# EVT_Rev_A_Shock_Measurement.net
KiCad netlist of a schematic drawn in EasyEDA Pro
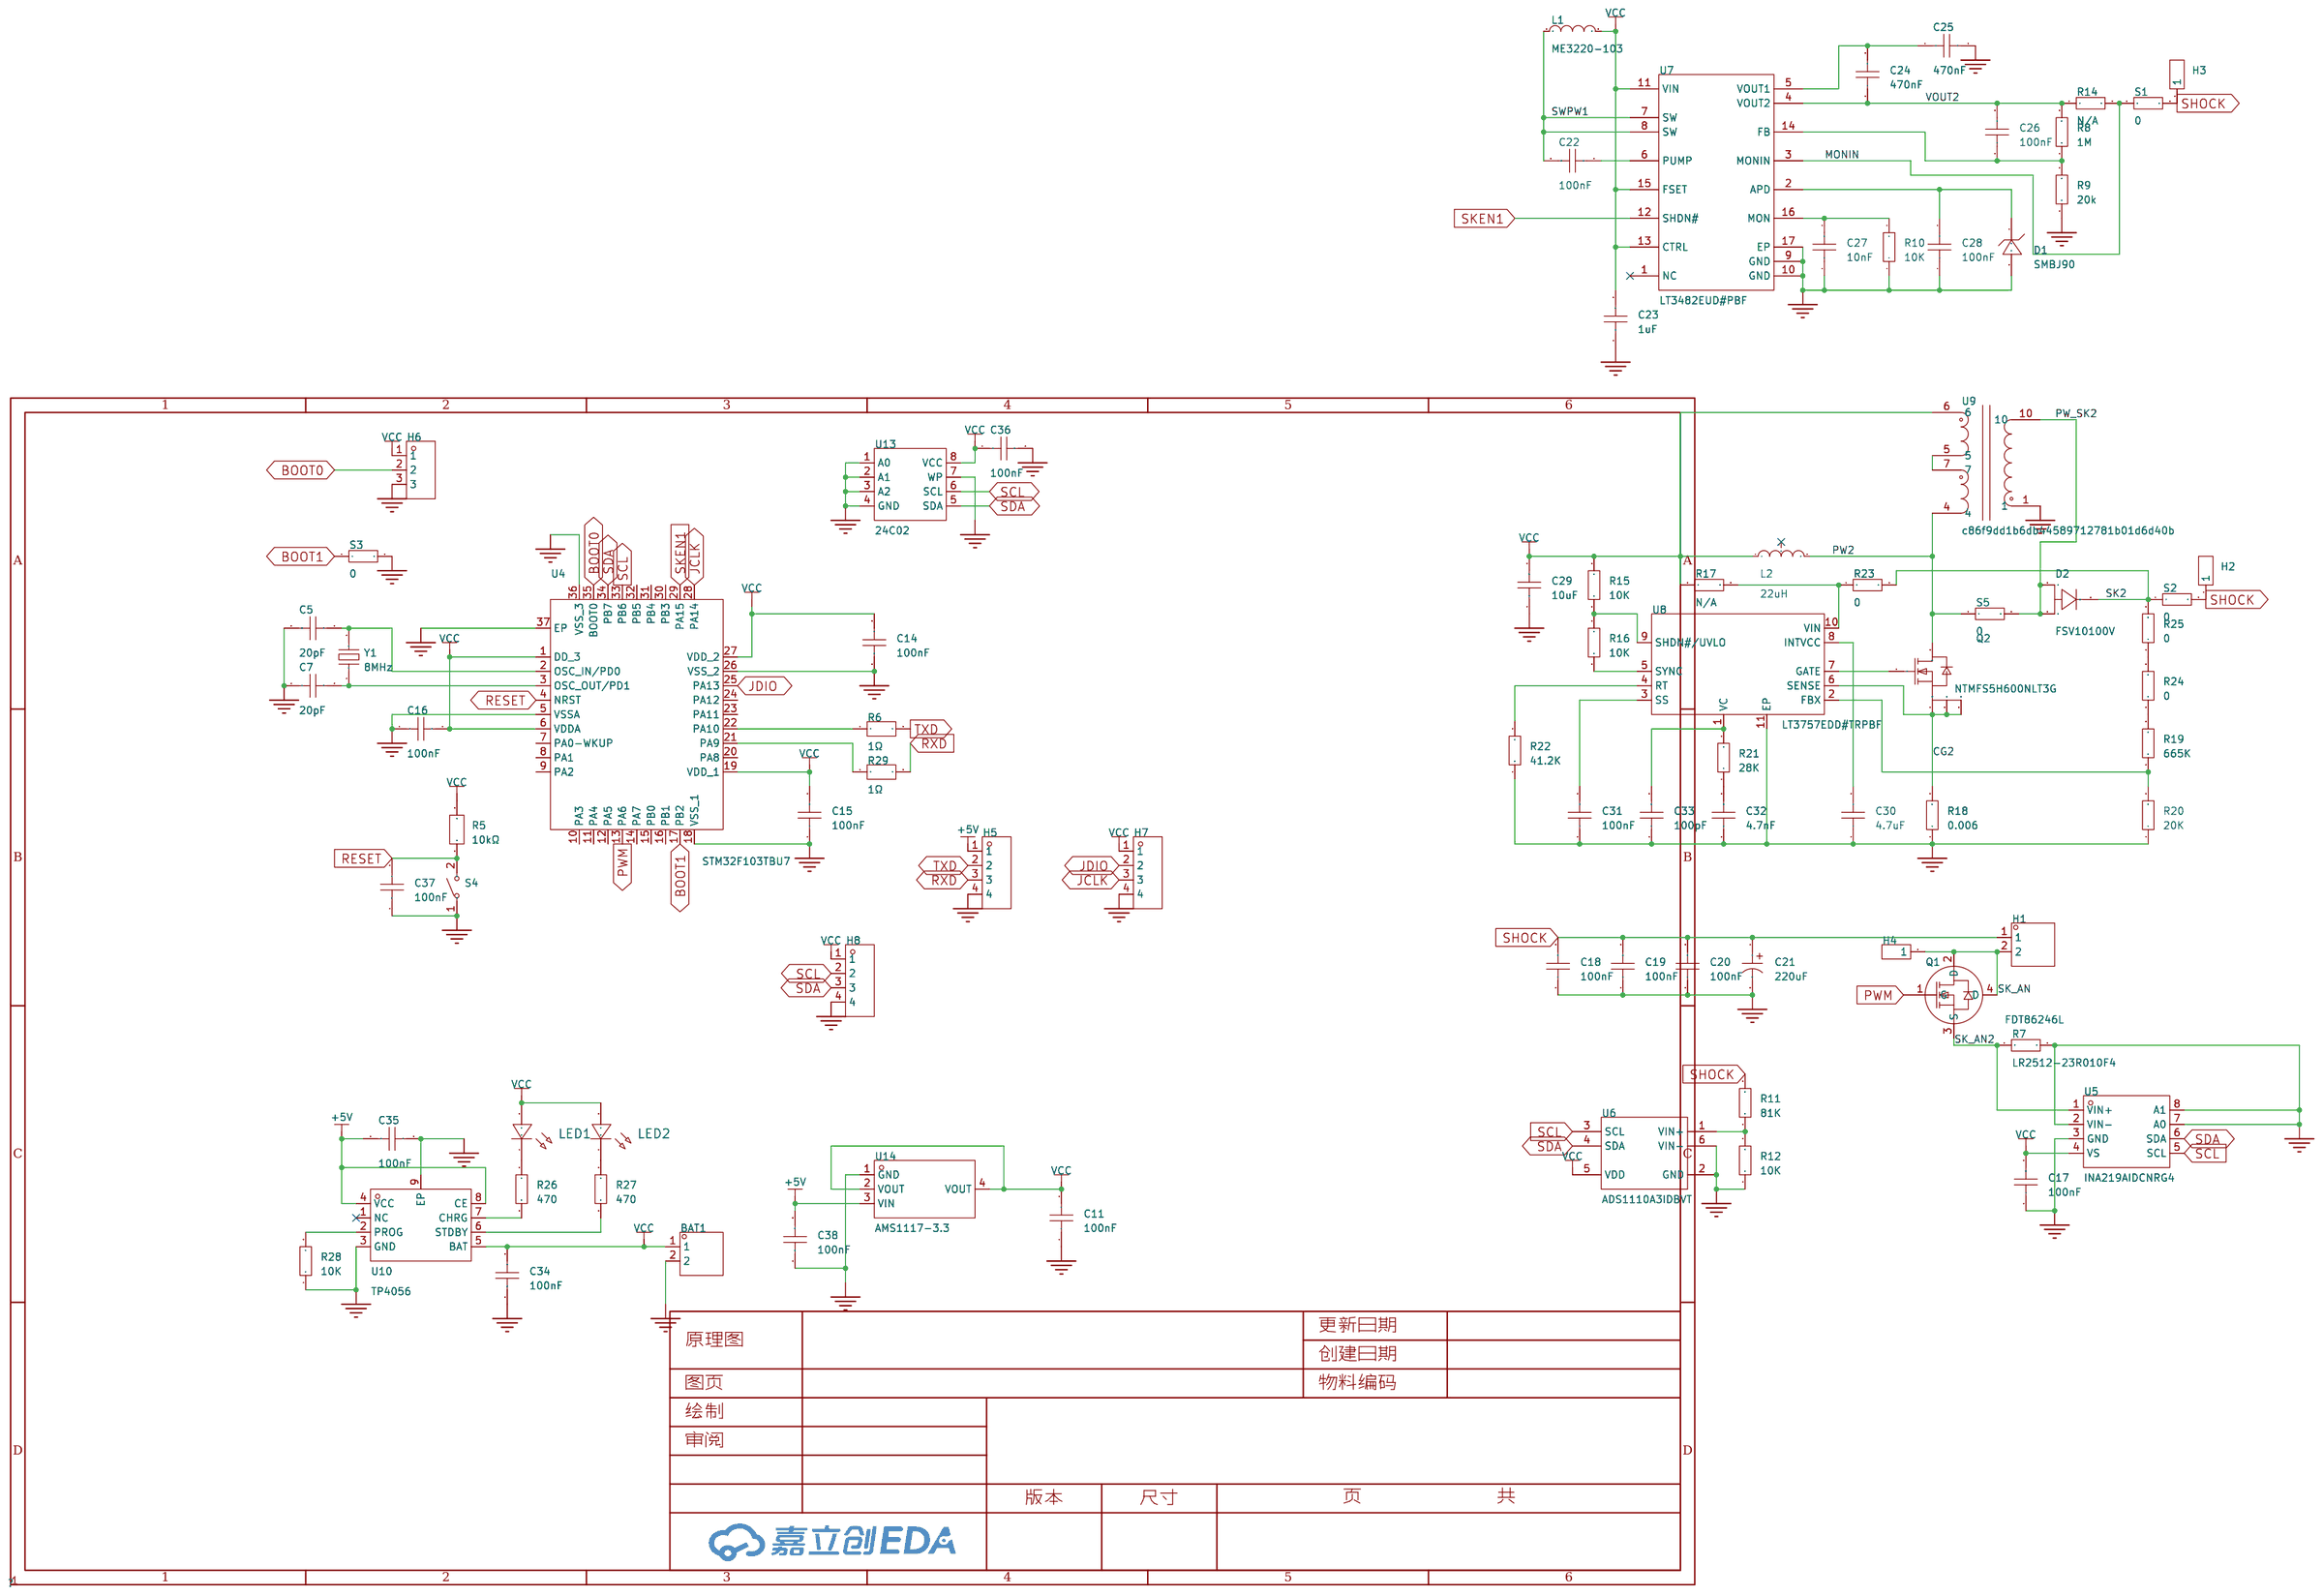
[diagram p0: schematic sheet]

(export (version "E")
  (design (tool "Eeschema 10.0.6"))
  (components
    (comp (ref "BAT1")
      (value "~")
      (footprint "easyedapro:HDR-TH_2P-P2.54-V-M-1")
      (libsource (lib "easyedapro") (part "210S-1*2P L=11.6MMGold-plated black"))
    )
    (comp (ref "C5")
      (value "20pF")
      (footprint "easyedapro:C0603")
      (description "容值:20pF;精度:±5%;额定电压:50V;材质(温度系数):C0G;")
      (fields
        (field (name "Manufacturer Part") "CSA0603C0G200J500JT")
        (field (name "Manufacturer") "HRE(芯声)")
      )
      (libsource (lib "easyedapro") (part "CSA0603C0G200J500JT"))
    )
    (comp (ref "C7")
      (value "20pF")
      (footprint "easyedapro:C0603")
      (description "容值:20pF;精度:±5%;额定电压:50V;材质(温度系数):C0G;")
      (fields
        (field (name "Manufacturer Part") "CSA0603C0G200J500JT")
        (field (name "Manufacturer") "HRE(芯声)")
      )
      (libsource (lib "easyedapro") (part "CSA0603C0G200J500JT"))
    )
    (comp (ref "C11")
      (value "100nF")
      (footprint "easyedapro:C0201")
      (description "容值:100nF;精度:±10%;额定电压:16V;材质(温度系数):X5R;")
      (fields (field (name "Manufacturer Part") "0201X104K160NT") (field (name "Manufacturer") "FH(风华)"))
      (libsource (lib "easyedapro") (part "0201X104K160NT"))
    )
    (comp (ref "C14")
      (value "100nF")
      (footprint "easyedapro:C1206")
      (libsource (lib "easyedapro") (part "CapAcitance"))
    )
    (comp (ref "C15")
      (value "100nF")
      (footprint "easyedapro:C1206")
      (libsource (lib "easyedapro") (part "CapAcitance"))
    )
    (comp (ref "C16")
      (value "100nF")
      (footprint "easyedapro:C1206")
      (libsource (lib "easyedapro") (part "CapAcitance"))
    )
    (comp (ref "C17")
      (value "100nF")
      (footprint "easyedapro:C1206")
      (libsource (lib "easyedapro") (part "CapAcitance"))
    )
    (comp (ref "C18")
      (value "100nF")
      (footprint "easyedapro:C1206")
      (libsource (lib "easyedapro") (part "CapAcitance"))
    )
    (comp (ref "C19")
      (value "100nF")
      (footprint "easyedapro:C1206")
      (libsource (lib "easyedapro") (part "CapAcitance"))
    )
    (comp (ref "C20")
      (value "100nF")
      (footprint "easyedapro:C1206")
      (libsource (lib "easyedapro") (part "CapAcitance"))
    )
    (comp (ref "C21")
      (value "220uF")
      (footprint "easyedapro:CAP-TH_BD8.0-P3.50-D0.6-FD")
      (description "容值:220uF;精度:±20%;额定电压:35V;纹波电流:2.9A@100Hz;等效串联电阻(ESR):28mΩ@100kHz;类型:-;")
      (fields (field (name "Manufacturer Part") "PA35V220M8x8") (field (name "Manufacturer") "捷而瑞"))
      (libsource (lib "easyedapro") (part "PA35V220M8X8"))
    )
    (comp (ref "C22")
      (value "100nF")
      (footprint "easyedapro:C1206")
      (libsource (lib "easyedapro") (part "CapAcitance"))
    )
    (comp (ref "C23")
      (value "1uF")
      (footprint "easyedapro:C1206")
      (libsource (lib "easyedapro") (part "CapAcitance"))
    )
    (comp (ref "C24")
      (value "470nF")
      (footprint "easyedapro:C1206")
      (libsource (lib "easyedapro") (part "CapAcitance"))
    )
    (comp (ref "C25")
      (value "470nF")
      (footprint "easyedapro:C1206")
      (libsource (lib "easyedapro") (part "CapAcitance"))
    )
    (comp (ref "C26")
      (value "100nF")
      (footprint "easyedapro:C1206")
      (libsource (lib "easyedapro") (part "CapAcitance"))
    )
    (comp (ref "C27")
      (value "10nF")
      (footprint "easyedapro:C1206")
      (libsource (lib "easyedapro") (part "CapAcitance"))
    )
    (comp (ref "C28")
      (value "100nF")
      (footprint "easyedapro:C1206")
      (libsource (lib "easyedapro") (part "CapAcitance"))
    )
    (comp (ref "C29")
      (value "10uF")
      (footprint "easyedapro:C1206")
      (libsource (lib "easyedapro") (part "CapAcitance"))
    )
    (comp (ref "C30")
      (value "4.7uF")
      (footprint "easyedapro:C1206")
      (libsource (lib "easyedapro") (part "CapAcitance"))
    )
    (comp (ref "C31")
      (value "100nF")
      (footprint "easyedapro:C1206")
      (libsource (lib "easyedapro") (part "CapAcitance"))
    )
    (comp (ref "C32")
      (value "4.7nF")
      (footprint "easyedapro:C1206")
      (libsource (lib "easyedapro") (part "CapAcitance"))
    )
    (comp (ref "C33")
      (value "100pF")
      (footprint "easyedapro:C1206")
      (libsource (lib "easyedapro") (part "CapAcitance"))
    )
    (comp (ref "C34")
      (value "100nF")
      (footprint "easyedapro:C1206")
      (libsource (lib "easyedapro") (part "CapAcitance"))
    )
    (comp (ref "C35")
      (value "100nF")
      (footprint "easyedapro:C1206")
      (libsource (lib "easyedapro") (part "CapAcitance"))
    )
    (comp (ref "C36")
      (value "100nF")
      (footprint "easyedapro:C0201")
      (description "容值:100nF;精度:±10%;额定电压:16V;材质(温度系数):X5R;")
      (fields (field (name "Manufacturer Part") "0201X104K160NT") (field (name "Manufacturer") "FH(风华)"))
      (libsource (lib "easyedapro") (part "0201X104K160NT"))
    )
    (comp (ref "C37")
      (value "100nF")
      (footprint "easyedapro:C1206")
      (libsource (lib "easyedapro") (part "CapAcitance"))
    )
    (comp (ref "C38")
      (value "100nF")
      (footprint "easyedapro:C0201")
      (description "容值:100nF;精度:±10%;额定电压:16V;材质(温度系数):X5R;")
      (fields (field (name "Manufacturer Part") "0201X104K160NT") (field (name "Manufacturer") "FH(风华)"))
      (libsource (lib "easyedapro") (part "0201X104K160NT"))
    )
    (comp (ref "D1")
      (value "SMBJ90")
      (footprint "easyedapro:SMB_L4.6-W3.6-LS5.3-RD")
      (fields (field (name "Manufacturer") "VISHAY(威世)"))
      (libsource (lib "easyedapro") (part "SMBJ24CD-M3/I"))
    )
    (comp (ref "D2")
      (value "FSV10100V")
      (footprint "easyedapro:TO-277A_L5.9-W4.4-LS6.5-TR")
      (description "二极管配置:独立式;正向压降(Vf):625mV@10A;直流反向耐压(Vr):100V;平均整流电流(Io):10A;")
      (fields (field (name "Manufacturer") "onsemi(安森美)"))
      (libsource (lib "easyedapro") (part "FSV10100V"))
    )
    (comp (ref "H1")
      (value "~")
      (footprint "easyedapro:HDR-TH_2P-P2.54-V-M-1")
      (libsource (lib "easyedapro") (part "210S-1*2P L=11.6MMGold-plated black"))
    )
    (comp (ref "H2")
      (value "~")
      (footprint "easyedapro:HDR-TH_1P-V-M_XKB_X4611WV-01I-C28D40")
      (libsource (lib "easyedapro") (part "HDR_1x1"))
    )
    (comp (ref "H3")
      (value "~")
      (footprint "easyedapro:HDR-TH_1P-V-M_XKB_X4611WV-01I-C28D40")
      (libsource (lib "easyedapro") (part "HDR_1x1"))
    )
    (comp (ref "H4")
      (value "~")
      (footprint "easyedapro:HDR-TH_1P-V-M_XKB_X4611WV-01I-C28D40")
      (libsource (lib "easyedapro") (part "HDR_1x1"))
    )
    (comp (ref "H5")
      (value "~")
      (footprint "easyedapro:HDR-TH_4P-P2.54-V-M")
      (libsource (lib "easyedapro") (part "PZ254V-11-04P"))
    )
    (comp (ref "H6")
      (value "~")
      (footprint "easyedapro:HDR-TH_3P-P2.54-V-M")
      (libsource (lib "easyedapro") (part "PZ254V-11-03P_C2937625"))
    )
    (comp (ref "H7")
      (value "~")
      (footprint "easyedapro:HDR-TH_4P-P2.54-V-M")
      (libsource (lib "easyedapro") (part "PZ254V-11-04P"))
    )
    (comp (ref "H8")
      (value "~")
      (footprint "easyedapro:HDR-TH_4P-P2.54-V-M")
      (libsource (lib "easyedapro") (part "PZ254V-11-04P"))
    )
    (comp (ref "L1")
      (value "ME3220-103")
      (footprint "easyedapro:IND-SMD_L3.2-W2.8")
      (fields (field (name "Manufacturer") "Coilcraft(线艺)"))
      (libsource (lib "easyedapro") (part "ME3220-222MLC"))
    )
    (comp (ref "L2")
      (value "22uH")
      (footprint "easyedapro:SMD-3_SER2915H-222KL")
      (description "电感值:22uH;精度:±10%;额定电流:20A;饱和电流(Isat):12A;")
      (fields
        (field (name "Manufacturer Part") "SER2918H-223KL")
        (field (name "Manufacturer") "Coilcraft(线艺)")
      )
      (libsource (lib "easyedapro") (part "SER2918H-223KL"))
    )
    (comp (ref "LED1")
      (value "~")
      (footprint "easyedapro:LED_0603")
      (libsource (lib "easyedapro") (part "LED_R"))
    )
    (comp (ref "LED2")
      (value "~")
      (footprint "easyedapro:LED_0603")
      (libsource (lib "easyedapro") (part "LED_R"))
    )
    (comp (ref "Q1")
      (value "FDT86246L")
      (footprint "easyedapro:SOT-223-4_L6.5-W3.5-P2.30-LS7.0-BR")
      (fields (field (name "Manufacturer") "onsemi(安森美)"))
      (libsource (lib "easyedapro") (part "FDT86246L"))
    )
    (comp (ref "Q2")
      (value "NTMFS5H600NLT3G")
      (footprint "easyedapro:DFN-5_L4.9-W5.9-P1.27-LS6.2-BL")
      (fields (field (name "Manufacturer") "onsemi(安森美)"))
      (libsource (lib "easyedapro") (part "NTMFS5H600NLT3G"))
    )
    (comp (ref "R5")
      (value "10kΩ")
      (footprint "easyedapro:R0603")
      (description "阻值:10kΩ;精度:±5%;功率:100mW;")
      (fields (field (name "Manufacturer Part") "RCA0310KJLF") (field (name "Manufacturer") "HKR(香港电阻)"))
      (libsource (lib "easyedapro") (part "RCA0310KJLF"))
    )
    (comp (ref "R6")
      (value "1Ω")
      (footprint "easyedapro:R0603")
      (description "电阻类型:厚膜电阻;阻值:1Ω;精度:±5%;功率:100mW;最大工作电压:75V;温度系数:±200ppm/°C;")
      (fields (field (name "Manufacturer Part") "FRC0603J1R0 TS") (field (name "Manufacturer") "FOJAN(富捷)"))
      (libsource (lib "easyedapro") (part "FRC0603J1R0 TS"))
    )
    (comp (ref "R7")
      (value "LR2512-23R010F4")
      (footprint "easyedapro:RES-SMD_L6.4-W3.2")
      (fields (field (name "Manufacturer") "RALEC(旺诠)"))
      (libsource (lib "easyedapro") (part "LR2512-23R010F4"))
    )
    (comp (ref "R8") (value "1M") (footprint "easyedapro:R1206") (libsource (lib "easyedapro") (part "电阻")))
    (comp (ref "R9") (value "20k") (footprint "easyedapro:R1206") (libsource (lib "easyedapro") (part "电阻")))
    (comp (ref "R10") (value "10K") (footprint "easyedapro:R1206") (libsource (lib "easyedapro") (part "电阻")))
    (comp (ref "R11") (value "81K") (footprint "easyedapro:R1206") (libsource (lib "easyedapro") (part "电阻")))
    (comp (ref "R12") (value "10K") (footprint "easyedapro:R1206") (libsource (lib "easyedapro") (part "电阻")))
    (comp (ref "R14") (value "N/A") (footprint "easyedapro:R1206") (libsource (lib "easyedapro") (part "电阻")))
    (comp (ref "R15") (value "10K") (footprint "easyedapro:R1206") (libsource (lib "easyedapro") (part "电阻")))
    (comp (ref "R16") (value "10K") (footprint "easyedapro:R1206") (libsource (lib "easyedapro") (part "电阻")))
    (comp (ref "R17") (value "N/A") (footprint "easyedapro:R1206") (libsource (lib "easyedapro") (part "电阻")))
    (comp (ref "R18")
      (value "0.006")
      (footprint "easyedapro:R1206")
      (libsource (lib "easyedapro") (part "电阻"))
    )
    (comp (ref "R19")
      (value "665K")
      (footprint "easyedapro:R1206")
      (libsource (lib "easyedapro") (part "电阻"))
    )
    (comp (ref "R20") (value "20K") (footprint "easyedapro:R1206") (libsource (lib "easyedapro") (part "电阻")))
    (comp (ref "R21") (value "28K") (footprint "easyedapro:R1206") (libsource (lib "easyedapro") (part "电阻")))
    (comp (ref "R22")
      (value "41.2K")
      (footprint "easyedapro:R1206")
      (libsource (lib "easyedapro") (part "电阻"))
    )
    (comp (ref "R23") (value "0") (footprint "easyedapro:R1206") (libsource (lib "easyedapro") (part "电阻")))
    (comp (ref "R24") (value "0") (footprint "easyedapro:R1206") (libsource (lib "easyedapro") (part "电阻")))
    (comp (ref "R25") (value "0") (footprint "easyedapro:R1206") (libsource (lib "easyedapro") (part "电阻")))
    (comp (ref "R26") (value "470") (footprint "easyedapro:R1206") (libsource (lib "easyedapro") (part "电阻")))
    (comp (ref "R27") (value "470") (footprint "easyedapro:R1206") (libsource (lib "easyedapro") (part "电阻")))
    (comp (ref "R28") (value "10K") (footprint "easyedapro:R1206") (libsource (lib "easyedapro") (part "电阻")))
    (comp (ref "R29")
      (value "1Ω")
      (footprint "easyedapro:R0603")
      (description "电阻类型:厚膜电阻;阻值:1Ω;精度:±5%;功率:100mW;最大工作电压:75V;温度系数:±200ppm/°C;")
      (fields (field (name "Manufacturer Part") "FRC0603J1R0 TS") (field (name "Manufacturer") "FOJAN(富捷)"))
      (libsource (lib "easyedapro") (part "FRC0603J1R0 TS"))
    )
    (comp (ref "S1") (value "0") (footprint "easyedapro:R1206") (libsource (lib "easyedapro") (part "电阻")))
    (comp (ref "S2") (value "0") (footprint "easyedapro:R1206") (libsource (lib "easyedapro") (part "电阻")))
    (comp (ref "S3") (value "0") (footprint "easyedapro:R1206") (libsource (lib "easyedapro") (part "电阻")))
    (comp (ref "S4")
      (value "GT-TC024S-H0060-L1")
      (footprint "easyedapro:SW-SMD_L3.0-W2.0-LS3.5")
      (description "作用力:1.6N;机械寿命:10万次;")
      (fields (field (name "Manufacturer") "G-Switch(品赞)"))
      (libsource (lib "easyedapro") (part "GT-TC024S-H0060-L1"))
    )
    (comp (ref "S5") (value "0") (footprint "easyedapro:R1206") (libsource (lib "easyedapro") (part "电阻")))
    (comp (ref "U4")
      (value "STM32F103TBU7")
      (footprint "easyedapro:UQFN-36_L6.0-W6.0-P0.50-BL-EP3.7")
      (description "CPU内核:ARM-M3;CPU最大主频:72MHz;应用领域:-;")
      (fields (field (name "Manufacturer") "ST(意法半导体)"))
      (libsource (lib "easyedapro") (part "STM32F103TBU7"))
    )
    (comp (ref "U5")
      (value "INA219AIDCNRG4")
      (footprint "easyedapro:SOT-23-8_L2.9-W1.6-P0.65-LS2.8-BR")
      (fields (field (name "Manufacturer") "TI(德州仪器)"))
      (libsource (lib "easyedapro") (part "INA219AIDCNRG4"))
    )
    (comp (ref "U6")
      (value "ADS1110A3IDBVT")
      (footprint "easyedapro:SOT-23-6_L2.9-W1.6-P0.95-LS2.8-BR")
      (description "接口:I2C;电源电压:2.7V~5.5V;采样率:240Hz;分辨率:16;")
      (fields (field (name "Manufacturer") "TI(德州仪器)"))
      (libsource (lib "easyedapro") (part "ADS1110A3IDBVT"))
    )
    (comp (ref "U7")
      (value "LT3482EUD#PBF")
      (footprint "easyedapro:QFN-16_L3.0-W3.0-P0.50-BL-EP1.7")
      (description "功能类型:升压型;输出类型:可调;工作电压:2.5V~16V;输出电压:5V~90V;输出电流:280mA;")
      (fields (field (name "Manufacturer") "ADI(亚德诺)"))
      (libsource (lib "easyedapro") (part "LT3482EUD#PBF"))
    )
    (comp (ref "U8")
      (value "LT3757EDD#TRPBF")
      (footprint "easyedapro:DFN-10_L3.0-W3.0-P0.50-BL-EP-1")
      (description "功能类型:升压型;工作电压:2.9V~40V;输出电流:-;")
      (fields (field (name "Manufacturer") "ADI(亚德诺)"))
      (libsource (lib "easyedapro") (part "LT3757EDD#TRPBF"))
    )
    (comp (ref "U9")
      (value "c86f9dd1b6db44589712781b01d6d40b")
      (libsource (lib "easyedapro") (part "DCT15EFD"))
    )
    (comp (ref "U10")
      (value "TP4056")
      (footprint "easyedapro:ESOP-8_L4.9-W3.9-P1.27-LS6.0-BL-EP-1")
      (description "工作电压:4.5V~8V;最大充电电流:1.2A;电池类型:锂离子;电池节数:1;")
      (fields (field (name "Manufacturer") "HXY MOSFET(华轩阳电子)"))
      (libsource (lib "easyedapro") (part "TP4056_C17702041"))
    )
    (comp (ref "U13")
      (value "24C02")
      (footprint "easyedapro:SOP-8_L4.9-W3.9-P1.27-LS6.0-BL")
      (description "24C02是电可擦除PROM，采用256x8-bit的组织架构，具有页写能力，每页为8字节。支持I2C总线传输协议，工作电压范围1.8V~5.5V，擦写寿命100万次，数据保持时间100年。")
      (fields (field (name "Manufacturer") "HX(恒佳兴)"))
      (libsource (lib "easyedapro") (part "24C02"))
    )
    (comp (ref "U14")
      (value "AMS1117-3.3")
      (footprint "easyedapro:SOT-223-3_L6.5-W3.4-P2.30-LS7.0-BR")
      (description "输出类型:固定;最大输入电压:-;输出电压:3.3V;最大输出电流:1A;电源纹波抑制比(PSRR):72dB@(120Hz);输出极性:正极;")
      (fields (field (name "Manufacturer") "AMS"))
      (libsource (lib "easyedapro") (part "AMS1117-3.3"))
    )
    (comp (ref "Y1")
      (value "8MHz")
      (footprint "easyedapro:CRYSTAL-SMD_L5.0-W3.2")
      (description "频率:8MHz;外接负载电容:20pF;频率稳定度(全温):±30ppm;")
      (fields
        (field (name "Manufacturer Part") "S50328M20PF10PPM2P")
        (field (name "Manufacturer") "SST(索斯特)")
      )
      (libsource (lib "easyedapro") (part "S50328M20PF10PPM2P"))
    )
  )
  (nets
    (net (code "1") (name "+5V") (class "Default")
      (node (ref "C35") (pin "1") (pinfunction "1_1") (pintype "input"))
      (node (ref "C38") (pin "2") (pinfunction "2_2") (pintype "unspecified"))
      (node (ref "H5") (pin "1") (pinfunction "1_1") (pintype "unspecified"))
      (node (ref "U10") (pin "4") (pinfunction "VCC_4") (pintype "unspecified"))
      (node (ref "U10") (pin "8") (pinfunction "CE_8") (pintype "unspecified"))
      (node (ref "U14") (pin "3") (pinfunction "VIN_3") (pintype "unspecified"))
    )
    (net (code "2") (name "/CG2") (class "Default")
      (node (ref "Q2") (pin "1") (pinfunction "S_1") (pintype "unspecified"))
      (node (ref "Q2") (pin "2") (pinfunction "S_2") (pintype "unspecified"))
      (node (ref "Q2") (pin "3") (pinfunction "S_3") (pintype "unspecified"))
      (node (ref "R18") (pin "2") (pinfunction "2_2") (pintype "input"))
      (node (ref "U8") (pin "6") (pinfunction "SENSE_6") (pintype "unspecified"))
    )
    (net (code "3") (name "/MONIN") (class "Default")
      (node (ref "R14") (pin "2") (pinfunction "2_2") (pintype "input"))
      (node (ref "S1") (pin "1") (pinfunction "1_1") (pintype "input"))
      (node (ref "U7") (pin "3") (pinfunction "MONIN_3") (pintype "unspecified"))
    )
    (net (code "4") (name "/PW2") (class "Default")
      (node (ref "L2") (pin "2") (pinfunction "2_2") (pintype "unspecified"))
      (node (ref "Q2") (pin "5") (pinfunction "D_5") (pintype "unspecified"))
      (node (ref "S5") (pin "1") (pinfunction "1_1") (pintype "input"))
      (node (ref "U9") (pin "4") (pinfunction "4_4") (pintype "input"))
    )
    (net (code "5") (name "/PW_SK2") (class "Default")
      (node (ref "D2") (pin "1") (pinfunction "1_1") (pintype "unspecified"))
      (node (ref "D2") (pin "2") (pinfunction "2_2") (pintype "unspecified"))
      (node (ref "S5") (pin "2") (pinfunction "2_2") (pintype "input"))
      (node (ref "U9") (pin "10") (pinfunction "10_10") (pintype "input"))
    )
    (net (code "6") (name "/SK2") (class "Default")
      (node (ref "D2") (pin "3") (pinfunction "3_3") (pintype "unspecified"))
      (node (ref "R23") (pin "2") (pinfunction "2_2") (pintype "input"))
      (node (ref "R25") (pin "2") (pinfunction "2_2") (pintype "input"))
      (node (ref "S2") (pin "1") (pinfunction "1_1") (pintype "input"))
    )
    (net (code "7") (name "/SK_AN") (class "Default")
      (node (ref "H1") (pin "2") (pinfunction "2_2") (pintype "unspecified"))
      (node (ref "H4") (pin "1") (pinfunction "1_1") (pintype "unspecified"))
      (node (ref "Q1") (pin "2") (pinfunction "D_2") (pintype "unspecified"))
      (node (ref "Q1") (pin "4") (pinfunction "D_4") (pintype "unspecified"))
    )
    (net (code "8") (name "/SK_AN2") (class "Default")
      (node (ref "Q1") (pin "3") (pinfunction "S_3") (pintype "unspecified"))
      (node (ref "R7") (pin "1") (pinfunction "1_1") (pintype "unspecified"))
      (node (ref "U5") (pin "1") (pinfunction "VIN+_1") (pintype "unspecified"))
    )
    (net (code "9") (name "/SWPW1") (class "Default")
      (node (ref "C22") (pin "2") (pinfunction "2_2") (pintype "input"))
      (node (ref "L1") (pin "1") (pinfunction "1_1") (pintype "unspecified"))
      (node (ref "U7") (pin "7") (pinfunction "SW_7") (pintype "unspecified"))
      (node (ref "U7") (pin "8") (pinfunction "SW_8") (pintype "unspecified"))
    )
    (net (code "10") (name "/VOUT2") (class "Default")
      (node (ref "C24") (pin "1") (pinfunction "1_1") (pintype "input"))
      (node (ref "C26") (pin "2") (pinfunction "2_2") (pintype "input"))
      (node (ref "R14") (pin "1") (pinfunction "1_1") (pintype "input"))
      (node (ref "R8") (pin "2") (pinfunction "2_2") (pintype "input"))
      (node (ref "U7") (pin "4") (pinfunction "VOUT2_4") (pintype "unspecified"))
    )
    (net (code "11") (name "BOOT0") (class "Default")
      (node (ref "H6") (pin "2") (pinfunction "2_2") (pintype "input"))
      (node (ref "U4") (pin "35") (pinfunction "BOOT0_35") (pintype "unspecified"))
    )
    (net (code "12") (name "BOOT1") (class "Default")
      (node (ref "S3") (pin "1") (pinfunction "1_1") (pintype "input"))
      (node (ref "U4") (pin "17") (pinfunction "PB2_17") (pintype "unspecified"))
    )
    (net (code "13") (name "GND") (class "Default")
      (node (ref "BAT1") (pin "2") (pinfunction "2_2") (pintype "unspecified"))
      (node (ref "C11") (pin "1") (pinfunction "1_1") (pintype "unspecified"))
      (node (ref "C14") (pin "1") (pinfunction "1_1") (pintype "input"))
      (node (ref "C15") (pin "1") (pinfunction "1_1") (pintype "input"))
      (node (ref "C16") (pin "1") (pinfunction "1_1") (pintype "input"))
      (node (ref "C17") (pin "1") (pinfunction "1_1") (pintype "input"))
      (node (ref "C18") (pin "1") (pinfunction "1_1") (pintype "input"))
      (node (ref "C19") (pin "1") (pinfunction "1_1") (pintype "input"))
      (node (ref "C20") (pin "1") (pinfunction "1_1") (pintype "input"))
      (node (ref "C21") (pin "2") (pinfunction "2_2") (pintype "input"))
      (node (ref "C23") (pin "1") (pinfunction "1_1") (pintype "input"))
      (node (ref "C25") (pin "2") (pinfunction "2_2") (pintype "input"))
      (node (ref "C27") (pin "1") (pinfunction "1_1") (pintype "input"))
      (node (ref "C28") (pin "1") (pinfunction "1_1") (pintype "input"))
      (node (ref "C29") (pin "1") (pinfunction "1_1") (pintype "input"))
      (node (ref "C30") (pin "1") (pinfunction "1_1") (pintype "input"))
      (node (ref "C31") (pin "1") (pinfunction "1_1") (pintype "input"))
      (node (ref "C32") (pin "1") (pinfunction "1_1") (pintype "input"))
      (node (ref "C33") (pin "1") (pinfunction "1_1") (pintype "input"))
      (node (ref "C34") (pin "1") (pinfunction "1_1") (pintype "input"))
      (node (ref "C35") (pin "2") (pinfunction "2_2") (pintype "input"))
      (node (ref "C36") (pin "2") (pinfunction "2_2") (pintype "unspecified"))
      (node (ref "C37") (pin "1") (pinfunction "1_1") (pintype "input"))
      (node (ref "C38") (pin "1") (pinfunction "1_1") (pintype "unspecified"))
      (node (ref "C5") (pin "1") (pinfunction "1_1") (pintype "unspecified"))
      (node (ref "C7") (pin "1") (pinfunction "1_1") (pintype "unspecified"))
      (node (ref "D1") (pin "2") (pinfunction "A_2") (pintype "unspecified"))
      (node (ref "H5") (pin "4") (pinfunction "4_4") (pintype "unspecified"))
      (node (ref "H6") (pin "3") (pinfunction "3_3") (pintype "input"))
      (node (ref "H7") (pin "4") (pinfunction "4_4") (pintype "unspecified"))
      (node (ref "H8") (pin "4") (pinfunction "4_4") (pintype "unspecified"))
      (node (ref "R10") (pin "1") (pinfunction "1_1") (pintype "input"))
      (node (ref "R12") (pin "1") (pinfunction "1_1") (pintype "input"))
      (node (ref "R18") (pin "1") (pinfunction "1_1") (pintype "input"))
      (node (ref "R20") (pin "1") (pinfunction "1_1") (pintype "input"))
      (node (ref "R22") (pin "1") (pinfunction "1_1") (pintype "input"))
      (node (ref "R28") (pin "1") (pinfunction "1_1") (pintype "input"))
      (node (ref "R7") (pin "2") (pinfunction "2_2") (pintype "unspecified"))
      (node (ref "R9") (pin "1") (pinfunction "1_1") (pintype "input"))
      (node (ref "S3") (pin "2") (pinfunction "2_2") (pintype "input"))
      (node (ref "S4") (pin "1") (pinfunction "1_1") (pintype "unspecified"))
      (node (ref "U10") (pin "3") (pinfunction "GND_3") (pintype "unspecified"))
      (node (ref "U10") (pin "9") (pinfunction "EP_9") (pintype "unspecified"))
      (node (ref "U13") (pin "1") (pinfunction "A0_1") (pintype "unspecified"))
      (node (ref "U13") (pin "2") (pinfunction "A1_2") (pintype "unspecified"))
      (node (ref "U13") (pin "3") (pinfunction "A2_3") (pintype "unspecified"))
      (node (ref "U13") (pin "4") (pinfunction "GND_4") (pintype "unspecified"))
      (node (ref "U13") (pin "7") (pinfunction "WP_7") (pintype "unspecified"))
      (node (ref "U14") (pin "1") (pinfunction "GND_1") (pintype "unspecified"))
      (node (ref "U4") (pin "18") (pinfunction "VSS_1_18") (pintype "unspecified"))
      (node (ref "U4") (pin "26") (pinfunction "VSS_2_26") (pintype "unspecified"))
      (node (ref "U4") (pin "36") (pinfunction "VSS_3_36") (pintype "unspecified"))
      (node (ref "U4") (pin "37") (pinfunction "EP_37") (pintype "unspecified"))
      (node (ref "U4") (pin "5") (pinfunction "VSSA_5") (pintype "unspecified"))
      (node (ref "U5") (pin "2") (pinfunction "VIN-_2") (pintype "unspecified"))
      (node (ref "U5") (pin "3") (pinfunction "GND_3") (pintype "unspecified"))
      (node (ref "U5") (pin "7") (pinfunction "A0_7") (pintype "unspecified"))
      (node (ref "U5") (pin "8") (pinfunction "A1_8") (pintype "unspecified"))
      (node (ref "U6") (pin "2") (pinfunction "GND_2") (pintype "unspecified"))
      (node (ref "U6") (pin "6") (pinfunction "VIN-_6") (pintype "unspecified"))
      (node (ref "U7") (pin "10") (pinfunction "GND_10") (pintype "unspecified"))
      (node (ref "U7") (pin "17") (pinfunction "EP_17") (pintype "unspecified"))
      (node (ref "U7") (pin "9") (pinfunction "GND_9") (pintype "unspecified"))
      (node (ref "U8") (pin "11") (pinfunction "EP_11") (pintype "unspecified"))
      (node (ref "U9") (pin "1") (pinfunction "1_1") (pintype "input"))
    )
    (net (code "14") (name "JCLK") (class "Default")
      (node (ref "H7") (pin "3") (pinfunction "3_3") (pintype "unspecified"))
      (node (ref "U4") (pin "28") (pinfunction "PA14_28") (pintype "unspecified"))
    )
    (net (code "15") (name "JDIO") (class "Default")
      (node (ref "H7") (pin "2") (pinfunction "2_2") (pintype "unspecified"))
      (node (ref "U4") (pin "25") (pinfunction "PA13_25") (pintype "unspecified"))
    )
    (net (code "16") (name "Net-(C32-Pad2)") (class "Default")
      (node (ref "C32") (pin "2") (pinfunction "2_2") (pintype "input"))
      (node (ref "R21") (pin "1") (pinfunction "1_1") (pintype "input"))
    )
    (net (code "17") (name "Net-(D1-K)") (class "Default")
      (node (ref "C28") (pin "2") (pinfunction "2_2") (pintype "input"))
      (node (ref "D1") (pin "1") (pinfunction "K_1") (pintype "unspecified"))
      (node (ref "U7") (pin "2") (pinfunction "APD_2") (pintype "unspecified"))
    )
    (net (code "18") (name "Net-(LED1-C)") (class "Default")
      (node (ref "LED1") (pin "1") (pinfunction "C_1") (pintype "input"))
      (node (ref "R26") (pin "2") (pinfunction "2_2") (pintype "input"))
    )
    (net (code "19") (name "Net-(LED2-C)") (class "Default")
      (node (ref "LED2") (pin "1") (pinfunction "C_1") (pintype "input"))
      (node (ref "R27") (pin "2") (pinfunction "2_2") (pintype "input"))
    )
    (net (code "20") (name "Net-(Q2-G)") (class "Default")
      (node (ref "Q2") (pin "4") (pinfunction "G_4") (pintype "unspecified"))
      (node (ref "U8") (pin "7") (pinfunction "GATE_7") (pintype "unspecified"))
    )
    (net (code "21") (name "Net-(R19-Pad2)") (class "Default")
      (node (ref "R19") (pin "2") (pinfunction "2_2") (pintype "input"))
      (node (ref "R24") (pin "1") (pinfunction "1_1") (pintype "input"))
    )
    (net (code "22") (name "Net-(R24-Pad2)") (class "Default")
      (node (ref "R24") (pin "2") (pinfunction "2_2") (pintype "input"))
      (node (ref "R25") (pin "1") (pinfunction "1_1") (pintype "input"))
    )
    (net (code "23") (name "Net-(U4-OSC_IN{slash}PD0)") (class "Default")
      (node (ref "C5") (pin "2") (pinfunction "2_2") (pintype "unspecified"))
      (node (ref "U4") (pin "2") (pinfunction "OSC_IN/PD0_2") (pintype "unspecified"))
      (node (ref "Y1") (pin "2") (pinfunction "2_2") (pintype "input"))
    )
    (net (code "24") (name "Net-(U4-OSC_OUT{slash}PD1)") (class "Default")
      (node (ref "C7") (pin "2") (pinfunction "2_2") (pintype "unspecified"))
      (node (ref "U4") (pin "3") (pinfunction "OSC_OUT/PD1_3") (pintype "unspecified"))
      (node (ref "Y1") (pin "1") (pinfunction "1_1") (pintype "input"))
    )
    (net (code "25") (name "Net-(U4-PA9)") (class "Default")
      (node (ref "R29") (pin "1") (pinfunction "1_1") (pintype "unspecified"))
      (node (ref "U4") (pin "21") (pinfunction "PA9_21") (pintype "unspecified"))
    )
    (net (code "26") (name "Net-(U4-PA10)") (class "Default")
      (node (ref "R6") (pin "1") (pinfunction "1_1") (pintype "unspecified"))
      (node (ref "U4") (pin "22") (pinfunction "PA10_22") (pintype "unspecified"))
    )
    (net (code "27") (name "Net-(U6-VIN+)") (class "Default")
      (node (ref "R11") (pin "1") (pinfunction "1_1") (pintype "input"))
      (node (ref "R12") (pin "2") (pinfunction "2_2") (pintype "input"))
      (node (ref "U6") (pin "1") (pinfunction "VIN+_1") (pintype "unspecified"))
    )
    (net (code "28") (name "Net-(U7-FB)") (class "Default")
      (node (ref "C26") (pin "1") (pinfunction "1_1") (pintype "input"))
      (node (ref "R8") (pin "1") (pinfunction "1_1") (pintype "input"))
      (node (ref "R9") (pin "2") (pinfunction "2_2") (pintype "input"))
      (node (ref "U7") (pin "14") (pinfunction "FB_14") (pintype "unspecified"))
    )
    (net (code "29") (name "Net-(U7-MON)") (class "Default")
      (node (ref "C27") (pin "2") (pinfunction "2_2") (pintype "input"))
      (node (ref "R10") (pin "2") (pinfunction "2_2") (pintype "input"))
      (node (ref "U7") (pin "16") (pinfunction "MON_16") (pintype "output"))
    )
    (net (code "30") (name "Net-(U7-PUMP)") (class "Default")
      (node (ref "C22") (pin "1") (pinfunction "1_1") (pintype "input"))
      (node (ref "U7") (pin "6") (pinfunction "PUMP_6") (pintype "unspecified"))
    )
    (net (code "31") (name "Net-(U7-VOUT1)") (class "Default")
      (node (ref "C24") (pin "2") (pinfunction "2_2") (pintype "input"))
      (node (ref "C25") (pin "1") (pinfunction "1_1") (pintype "input"))
      (node (ref "U7") (pin "5") (pinfunction "VOUT1_5") (pintype "unspecified"))
    )
    (net (code "32") (name "Net-(U8-FBX)") (class "Default")
      (node (ref "R19") (pin "1") (pinfunction "1_1") (pintype "input"))
      (node (ref "R20") (pin "2") (pinfunction "2_2") (pintype "input"))
      (node (ref "U8") (pin "2") (pinfunction "FBX_2") (pintype "unspecified"))
    )
    (net (code "33") (name "Net-(U8-INTVCC)") (class "Default")
      (node (ref "C30") (pin "2") (pinfunction "2_2") (pintype "input"))
      (node (ref "U8") (pin "8") (pinfunction "INTVCC_8") (pintype "unspecified"))
    )
    (net (code "34") (name "Net-(U8-RT)") (class "Default")
      (node (ref "R22") (pin "2") (pinfunction "2_2") (pintype "input"))
      (node (ref "U8") (pin "4") (pinfunction "RT_4") (pintype "unspecified"))
    )
    (net (code "35") (name "Net-(U8-SHDN#{slash}UVLO)") (class "Default")
      (node (ref "R15") (pin "1") (pinfunction "1_1") (pintype "input"))
      (node (ref "R16") (pin "2") (pinfunction "2_2") (pintype "input"))
      (node (ref "U8") (pin "9") (pinfunction "SHDN#/UVLO_9") (pintype "unspecified"))
    )
    (net (code "36") (name "Net-(U8-SS)") (class "Default")
      (node (ref "C31") (pin "2") (pinfunction "2_2") (pintype "input"))
      (node (ref "U8") (pin "3") (pinfunction "SS_3") (pintype "unspecified"))
    )
    (net (code "37") (name "Net-(U8-SYNC)") (class "Default")
      (node (ref "R16") (pin "1") (pinfunction "1_1") (pintype "input"))
      (node (ref "U8") (pin "5") (pinfunction "SYNC_5") (pintype "unspecified"))
    )
    (net (code "38") (name "Net-(U8-VC)") (class "Default")
      (node (ref "C33") (pin "2") (pinfunction "2_2") (pintype "input"))
      (node (ref "R21") (pin "2") (pinfunction "2_2") (pintype "input"))
      (node (ref "U8") (pin "1") (pinfunction "VC_1") (pintype "unspecified"))
    )
    (net (code "39") (name "Net-(U8-VIN)") (class "Default")
      (node (ref "R17") (pin "2") (pinfunction "2_2") (pintype "input"))
      (node (ref "R23") (pin "1") (pinfunction "1_1") (pintype "input"))
      (node (ref "U8") (pin "10") (pinfunction "VIN_10") (pintype "unspecified"))
    )
    (net (code "40") (name "Net-(U9-Pad5)") (class "Default")
      (node (ref "U9") (pin "5") (pinfunction "5_5") (pintype "input"))
      (node (ref "U9") (pin "7") (pinfunction "7_7") (pintype "input"))
    )
    (net (code "41") (name "Net-(U10-CHRG)") (class "Default")
      (node (ref "R26") (pin "1") (pinfunction "1_1") (pintype "input"))
      (node (ref "U10") (pin "7") (pinfunction "CHRG_7") (pintype "unspecified"))
    )
    (net (code "42") (name "Net-(U10-PROG)") (class "Default")
      (node (ref "R28") (pin "2") (pinfunction "2_2") (pintype "input"))
      (node (ref "U10") (pin "2") (pinfunction "PROG_2") (pintype "unspecified"))
    )
    (net (code "43") (name "Net-(U10-STDBY)") (class "Default")
      (node (ref "R27") (pin "1") (pinfunction "1_1") (pintype "input"))
      (node (ref "U10") (pin "6") (pinfunction "STDBY_6") (pintype "unspecified"))
    )
    (net (code "44") (name "PWM") (class "Default")
      (node (ref "Q1") (pin "1") (pinfunction "G_1") (pintype "unspecified"))
      (node (ref "U4") (pin "13") (pinfunction "PA6_13") (pintype "unspecified"))
    )
    (net (code "45") (name "RESET") (class "Default")
      (node (ref "C37") (pin "2") (pinfunction "2_2") (pintype "input"))
      (node (ref "R5") (pin "1") (pinfunction "1_1") (pintype "unspecified"))
      (node (ref "S4") (pin "2") (pinfunction "2_2") (pintype "unspecified"))
      (node (ref "U4") (pin "4") (pinfunction "NRST_4") (pintype "unspecified"))
    )
    (net (code "46") (name "RXD") (class "Default")
      (node (ref "H5") (pin "3") (pinfunction "3_3") (pintype "unspecified"))
      (node (ref "R29") (pin "2") (pinfunction "2_2") (pintype "unspecified"))
    )
    (net (code "47") (name "SCL") (class "Default")
      (node (ref "H8") (pin "2") (pinfunction "2_2") (pintype "unspecified"))
      (node (ref "U13") (pin "6") (pinfunction "SCL_6") (pintype "unspecified"))
      (node (ref "U4") (pin "33") (pinfunction "PB6_33") (pintype "unspecified"))
      (node (ref "U5") (pin "5") (pinfunction "SCL_5") (pintype "unspecified"))
      (node (ref "U6") (pin "3") (pinfunction "SCL_3") (pintype "unspecified"))
    )
    (net (code "48") (name "SDA") (class "Default")
      (node (ref "H8") (pin "3") (pinfunction "3_3") (pintype "unspecified"))
      (node (ref "U13") (pin "5") (pinfunction "SDA_5") (pintype "unspecified"))
      (node (ref "U4") (pin "34") (pinfunction "PB7_34") (pintype "unspecified"))
      (node (ref "U5") (pin "6") (pinfunction "SDA_6") (pintype "unspecified"))
      (node (ref "U6") (pin "4") (pinfunction "SDA_4") (pintype "bidirectional"))
    )
    (net (code "49") (name "SHOCK") (class "Default")
      (node (ref "C18") (pin "2") (pinfunction "2_2") (pintype "input"))
      (node (ref "C19") (pin "2") (pinfunction "2_2") (pintype "input"))
      (node (ref "C20") (pin "2") (pinfunction "2_2") (pintype "input"))
      (node (ref "C21") (pin "1") (pinfunction "1_1") (pintype "input"))
      (node (ref "H1") (pin "1") (pinfunction "1_1") (pintype "unspecified"))
      (node (ref "H2") (pin "1") (pinfunction "1_1") (pintype "unspecified"))
      (node (ref "H3") (pin "1") (pinfunction "1_1") (pintype "unspecified"))
      (node (ref "R11") (pin "2") (pinfunction "2_2") (pintype "input"))
      (node (ref "S1") (pin "2") (pinfunction "2_2") (pintype "input"))
      (node (ref "S2") (pin "2") (pinfunction "2_2") (pintype "input"))
    )
    (net (code "50") (name "SKEN1") (class "Default")
      (node (ref "U4") (pin "29") (pinfunction "PA15_29") (pintype "unspecified"))
      (node (ref "U7") (pin "12") (pinfunction "SHDN#_12") (pintype "unspecified"))
    )
    (net (code "51") (name "TXD") (class "Default")
      (node (ref "H5") (pin "2") (pinfunction "2_2") (pintype "unspecified"))
      (node (ref "R6") (pin "2") (pinfunction "2_2") (pintype "unspecified"))
    )
    (net (code "52") (name "VCC") (class "Default")
      (node (ref "BAT1") (pin "1") (pinfunction "1_1") (pintype "unspecified"))
      (node (ref "C11") (pin "2") (pinfunction "2_2") (pintype "unspecified"))
      (node (ref "C14") (pin "2") (pinfunction "2_2") (pintype "input"))
      (node (ref "C15") (pin "2") (pinfunction "2_2") (pintype "input"))
      (node (ref "C16") (pin "2") (pinfunction "2_2") (pintype "input"))
      (node (ref "C17") (pin "2") (pinfunction "2_2") (pintype "input"))
      (node (ref "C23") (pin "2") (pinfunction "2_2") (pintype "input"))
      (node (ref "C29") (pin "2") (pinfunction "2_2") (pintype "input"))
      (node (ref "C34") (pin "2") (pinfunction "2_2") (pintype "input"))
      (node (ref "C36") (pin "1") (pinfunction "1_1") (pintype "unspecified"))
      (node (ref "H6") (pin "1") (pinfunction "1_1") (pintype "input"))
      (node (ref "H7") (pin "1") (pinfunction "1_1") (pintype "unspecified"))
      (node (ref "H8") (pin "1") (pinfunction "1_1") (pintype "unspecified"))
      (node (ref "L1") (pin "2") (pinfunction "2_2") (pintype "unspecified"))
      (node (ref "L2") (pin "1") (pinfunction "1_1") (pintype "unspecified"))
      (node (ref "LED1") (pin "2") (pinfunction "A_2") (pintype "input"))
      (node (ref "LED2") (pin "2") (pinfunction "A_2") (pintype "input"))
      (node (ref "R15") (pin "2") (pinfunction "2_2") (pintype "input"))
      (node (ref "R17") (pin "1") (pinfunction "1_1") (pintype "input"))
      (node (ref "R5") (pin "2") (pinfunction "2_2") (pintype "unspecified"))
      (node (ref "U10") (pin "5") (pinfunction "BAT_5") (pintype "unspecified"))
      (node (ref "U13") (pin "8") (pinfunction "VCC_8") (pintype "unspecified"))
      (node (ref "U14") (pin "2") (pinfunction "VOUT_2") (pintype "unspecified"))
      (node (ref "U14") (pin "4") (pinfunction "VOUT_4") (pintype "unspecified"))
      (node (ref "U4") (pin "1") (pinfunction "DD_3_1") (pintype "unspecified"))
      (node (ref "U4") (pin "19") (pinfunction "VDD_1_19") (pintype "unspecified"))
      (node (ref "U4") (pin "27") (pinfunction "VDD_2_27") (pintype "unspecified"))
      (node (ref "U4") (pin "6") (pinfunction "VDDA_6") (pintype "unspecified"))
      (node (ref "U5") (pin "4") (pinfunction "VS_4") (pintype "unspecified"))
      (node (ref "U6") (pin "5") (pinfunction "VDD_5") (pintype "unspecified"))
      (node (ref "U7") (pin "11") (pinfunction "VIN_11") (pintype "unspecified"))
      (node (ref "U7") (pin "13") (pinfunction "CTRL_13") (pintype "unspecified"))
      (node (ref "U7") (pin "15") (pinfunction "FSET_15") (pintype "unspecified"))
      (node (ref "U9") (pin "6") (pinfunction "6_6") (pintype "input"))
    )
    (net (code "53") (name "unconnected-(L2-Pad3)") (class "Default")
      (node (ref "L2") (pin "3") (pinfunction "3_3") (pintype "unspecified+no_connect"))
    )
    (net (code "54") (name "unconnected-(U4-PA0-WKUP-Pad7)") (class "Default")
      (node (ref "U4") (pin "7") (pinfunction "PA0-WKUP_7") (pintype "unspecified"))
    )
    (net (code "55") (name "unconnected-(U4-PA1-Pad8)") (class "Default")
      (node (ref "U4") (pin "8") (pinfunction "PA1_8") (pintype "unspecified"))
    )
    (net (code "56") (name "unconnected-(U4-PA2-Pad9)") (class "Default")
      (node (ref "U4") (pin "9") (pinfunction "PA2_9") (pintype "unspecified"))
    )
    (net (code "57") (name "unconnected-(U4-PA3-Pad10)") (class "Default")
      (node (ref "U4") (pin "10") (pinfunction "PA3_10") (pintype "unspecified"))
    )
    (net (code "58") (name "unconnected-(U4-PA4-Pad11)") (class "Default")
      (node (ref "U4") (pin "11") (pinfunction "PA4_11") (pintype "unspecified"))
    )
    (net (code "59") (name "unconnected-(U4-PA5-Pad12)") (class "Default")
      (node (ref "U4") (pin "12") (pinfunction "PA5_12") (pintype "unspecified"))
    )
    (net (code "60") (name "unconnected-(U4-PA7-Pad14)") (class "Default")
      (node (ref "U4") (pin "14") (pinfunction "PA7_14") (pintype "unspecified"))
    )
    (net (code "61") (name "unconnected-(U4-PA8-Pad20)") (class "Default")
      (node (ref "U4") (pin "20") (pinfunction "PA8_20") (pintype "unspecified"))
    )
    (net (code "62") (name "unconnected-(U4-PA11-Pad23)") (class "Default")
      (node (ref "U4") (pin "23") (pinfunction "PA11_23") (pintype "unspecified"))
    )
    (net (code "63") (name "unconnected-(U4-PA12-Pad24)") (class "Default")
      (node (ref "U4") (pin "24") (pinfunction "PA12_24") (pintype "unspecified"))
    )
    (net (code "64") (name "unconnected-(U4-PB0-Pad15)") (class "Default")
      (node (ref "U4") (pin "15") (pinfunction "PB0_15") (pintype "unspecified"))
    )
    (net (code "65") (name "unconnected-(U4-PB1-Pad16)") (class "Default")
      (node (ref "U4") (pin "16") (pinfunction "PB1_16") (pintype "unspecified"))
    )
    (net (code "66") (name "unconnected-(U4-PB3-Pad30)") (class "Default")
      (node (ref "U4") (pin "30") (pinfunction "PB3_30") (pintype "unspecified"))
    )
    (net (code "67") (name "unconnected-(U4-PB4-Pad31)") (class "Default")
      (node (ref "U4") (pin "31") (pinfunction "PB4_31") (pintype "unspecified"))
    )
    (net (code "68") (name "unconnected-(U4-PB5-Pad32)") (class "Default")
      (node (ref "U4") (pin "32") (pinfunction "PB5_32") (pintype "unspecified"))
    )
    (net (code "69") (name "unconnected-(U7-NC-Pad1)") (class "Default")
      (node (ref "U7") (pin "1") (pinfunction "NC_1") (pintype "unspecified+no_connect"))
    )
    (net (code "70") (name "unconnected-(U10-NC-Pad1)") (class "Default")
      (node (ref "U10") (pin "1") (pinfunction "NC_1") (pintype "unspecified+no_connect"))
    )
  )
)
